# Inverter-demo_1.net
KiCad netlist of a schematic drawn in EAGLE
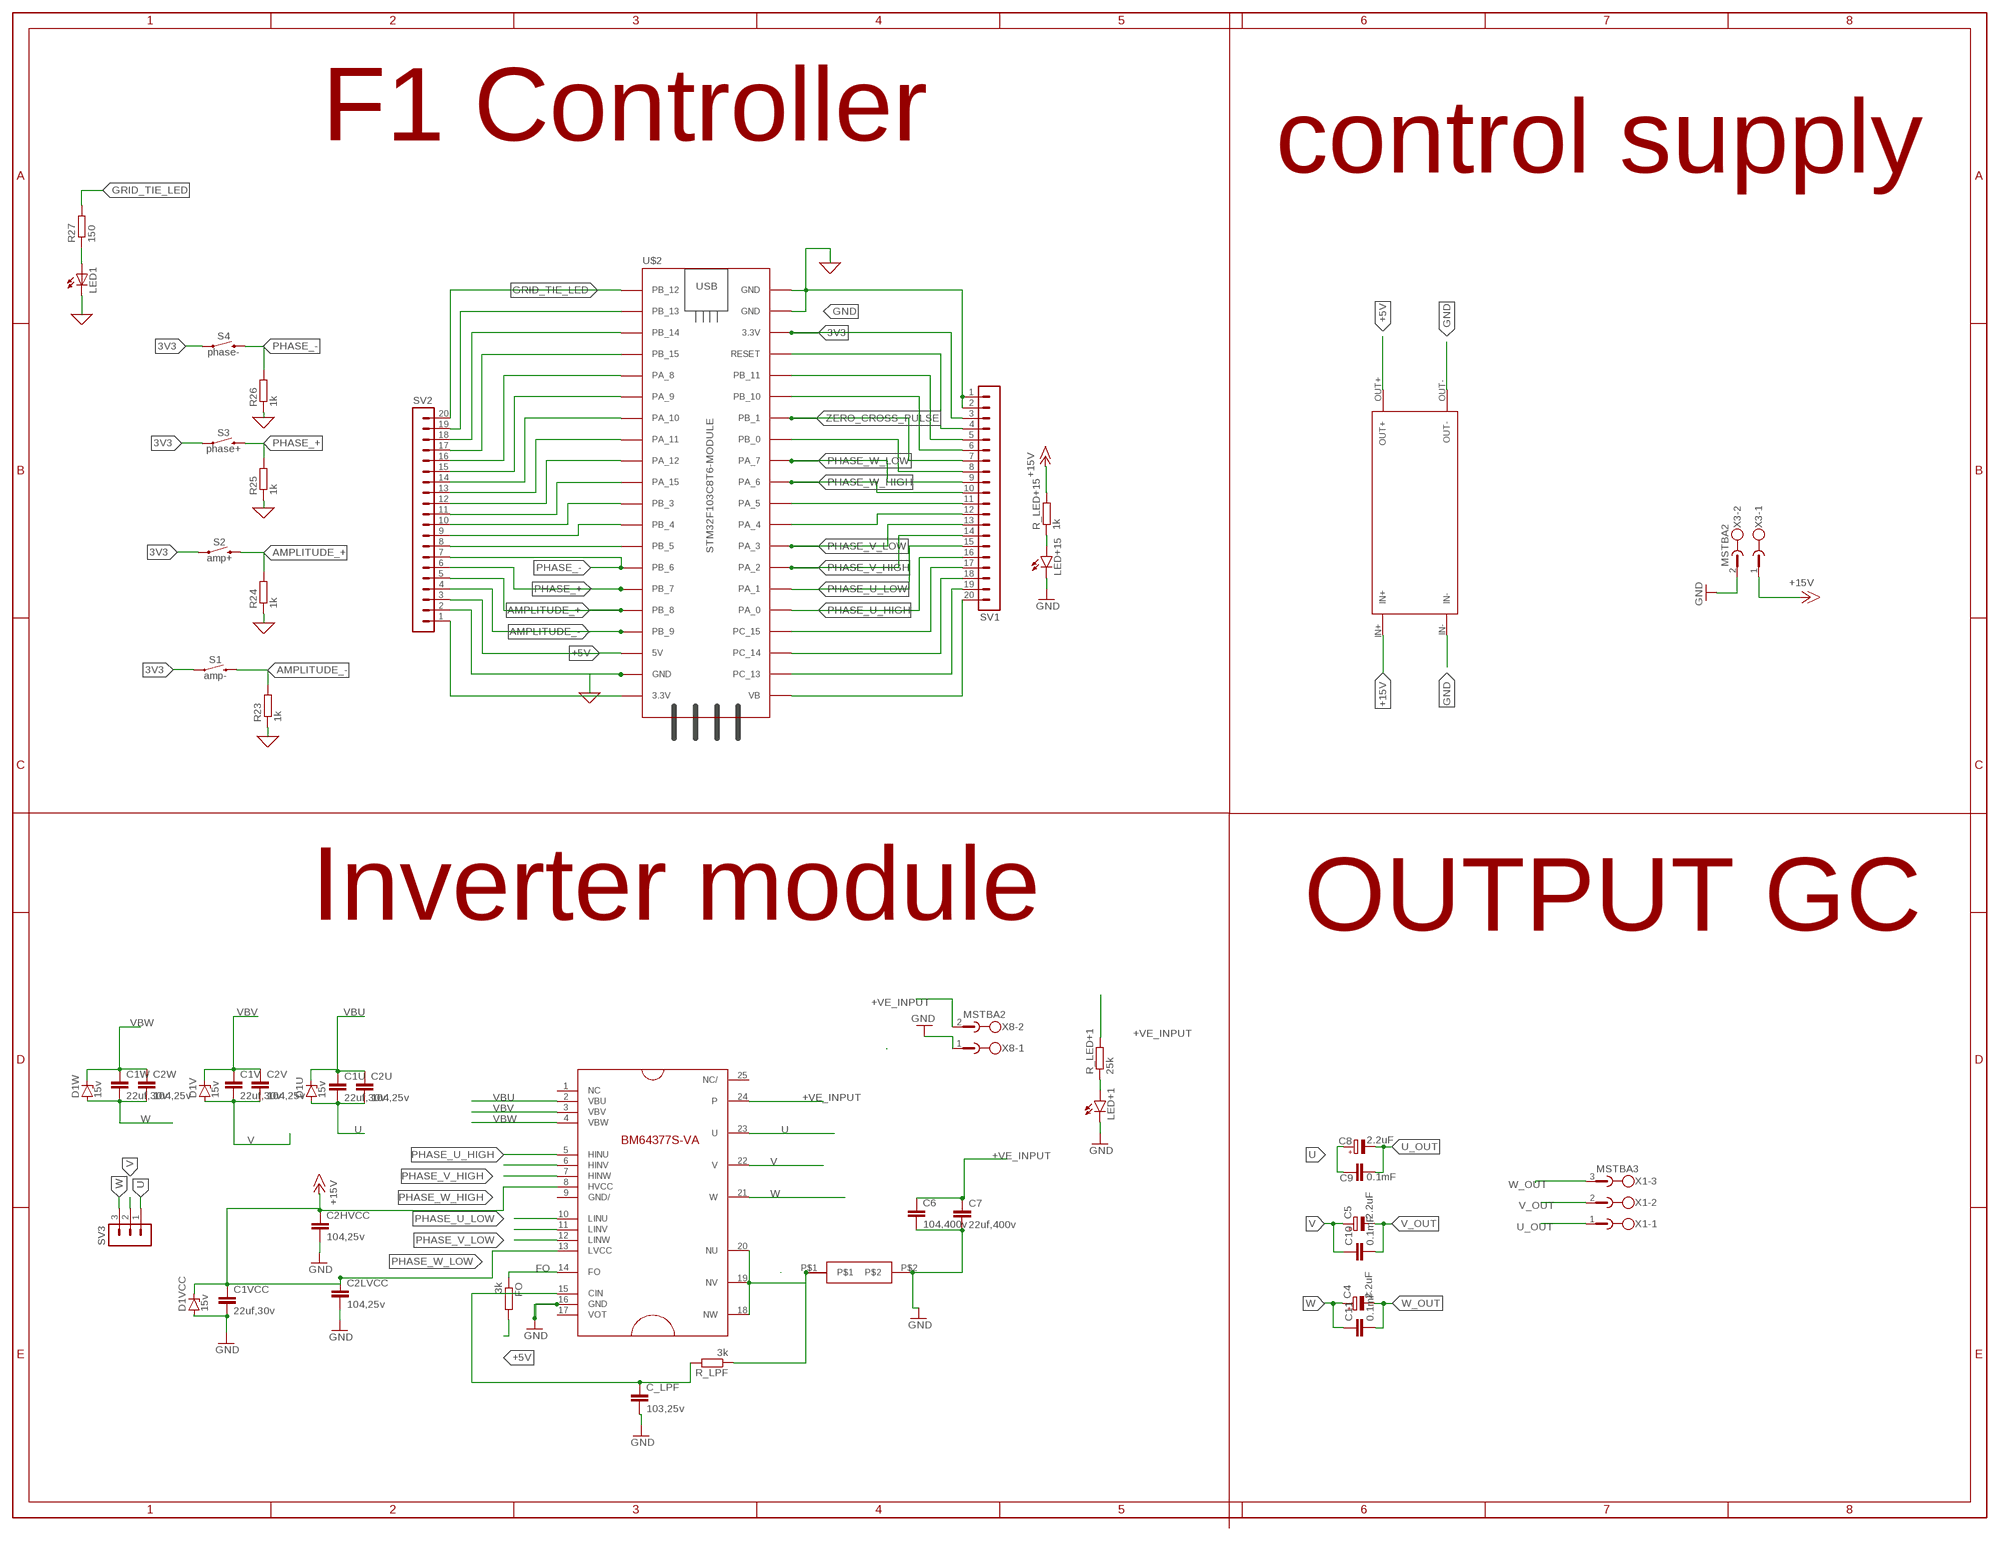
[diagram p0: schematic, sheet 1]

(export (version "E")
  (design (tool "Eeschema 10.0.6"))
  (components
    (comp (ref "C1U")
      (value "22uf,30v")
      (footprint "eagle-import:C050-025X075")
      (libsource (lib "eagle-import") (part "C-EU050-025X075"))
    )
    (comp (ref "C1V")
      (value "22uf,30v")
      (footprint "eagle-import:C050-025X075")
      (libsource (lib "eagle-import") (part "C-EU050-025X075"))
    )
    (comp (ref "C1VCC")
      (value "22uf,30v")
      (footprint "eagle-import:C050-025X075")
      (libsource (lib "eagle-import") (part "C-EU050-025X075"))
    )
    (comp (ref "C1W")
      (value "22uf,30v")
      (footprint "eagle-import:C050-025X075")
      (libsource (lib "eagle-import") (part "C-EU050-025X075"))
    )
    (comp (ref "C2HVCC")
      (value "104,25v")
      (footprint "eagle-import:C050-025X075")
      (libsource (lib "eagle-import") (part "C-EU050-025X075"))
    )
    (comp (ref "C2LVCC")
      (value "104,25v")
      (footprint "eagle-import:C050-025X075")
      (libsource (lib "eagle-import") (part "C-EU050-025X075"))
    )
    (comp (ref "C2U")
      (value "104,25v")
      (footprint "eagle-import:C050-025X075")
      (libsource (lib "eagle-import") (part "C-EU050-025X075"))
    )
    (comp (ref "C2V")
      (value "104,25v")
      (footprint "eagle-import:C050-025X075")
      (libsource (lib "eagle-import") (part "C-EU050-025X075"))
    )
    (comp (ref "C2W")
      (value "104,25v")
      (footprint "eagle-import:C050-025X075")
      (libsource (lib "eagle-import") (part "C-EU050-025X075"))
    )
    (comp (ref "C4")
      (value "2.2uF")
      (footprint "eagle-import:E3,5-8")
      (libsource (lib "eagle-import") (part "CPOL-EUE3.5-8"))
    )
    (comp (ref "C5")
      (value "2.2uF")
      (footprint "eagle-import:E3,5-8")
      (libsource (lib "eagle-import") (part "CPOL-EUE3.5-8"))
    )
    (comp (ref "C6")
      (value "104,400v")
      (footprint "eagle-import:C050-025X075")
      (libsource (lib "eagle-import") (part "C-EU050-025X075"))
    )
    (comp (ref "C7")
      (value "22uf,400v")
      (footprint "eagle-import:C050-025X075")
      (libsource (lib "eagle-import") (part "C-EU050-025X075"))
    )
    (comp (ref "C8")
      (value "2.2uF")
      (footprint "eagle-import:E3,5-8")
      (libsource (lib "eagle-import") (part "CPOL-EUE3.5-8"))
    )
    (comp (ref "C9")
      (value "0.1mF")
      (footprint "eagle-import:C5B5")
      (libsource (lib "eagle-import") (part "C5/5"))
    )
    (comp (ref "C10")
      (value "0.1mF")
      (footprint "eagle-import:C5B5")
      (libsource (lib "eagle-import") (part "C5/5"))
    )
    (comp (ref "C11")
      (value "0.1mF")
      (footprint "eagle-import:C5B5")
      (libsource (lib "eagle-import") (part "C5/5"))
    )
    (comp (ref "C_LPF")
      (value "103,25v")
      (footprint "eagle-import:C050-025X075")
      (libsource (lib "eagle-import") (part "C-EU050-025X075"))
    )
    (comp (ref "D1U")
      (value "15v")
      (footprint "eagle-import:DO34Z7")
      (libsource (lib "eagle-import") (part "ZENER-DIODEDO34-7"))
    )
    (comp (ref "D1V")
      (value "15v")
      (footprint "eagle-import:DO34Z7")
      (libsource (lib "eagle-import") (part "ZENER-DIODEDO34-7"))
    )
    (comp (ref "D1VCC")
      (value "15v")
      (footprint "eagle-import:DO34Z7")
      (libsource (lib "eagle-import") (part "ZENER-DIODEDO34-7"))
    )
    (comp (ref "D1W")
      (value "15v")
      (footprint "eagle-import:DO34Z7")
      (libsource (lib "eagle-import") (part "ZENER-DIODEDO34-7"))
    )
    (comp (ref "FO")
      (value "3k")
      (footprint "eagle-import:0207_10")
      (libsource (lib "eagle-import") (part "R-EU_0207/10"))
    )
    (comp (ref "LED+1")
      (value "LED5MM")
      (footprint "eagle-import:LED5MM")
      (libsource (lib "eagle-import") (part "led_259_LED5MM"))
    )
    (comp (ref "LED+15")
      (value "LED5MM")
      (footprint "eagle-import:LED5MM")
      (libsource (lib "eagle-import") (part "led_259_LED5MM"))
    )
    (comp (ref "LED1")
      (value "LED3MM")
      (footprint "eagle-import:LED3MM")
      (libsource (lib "eagle-import") (part "LED3MM"))
    )
    (comp (ref "R23")
      (value "1k")
      (footprint "eagle-import:0207_10")
      (libsource (lib "eagle-import") (part "R-EU_0207/10"))
    )
    (comp (ref "R24")
      (value "1k")
      (footprint "eagle-import:0207_10")
      (libsource (lib "eagle-import") (part "R-EU_0207/10"))
    )
    (comp (ref "R25")
      (value "1k")
      (footprint "eagle-import:0207_10")
      (libsource (lib "eagle-import") (part "R-EU_0207/10"))
    )
    (comp (ref "R26")
      (value "1k")
      (footprint "eagle-import:0207_10")
      (libsource (lib "eagle-import") (part "R-EU_0207/10"))
    )
    (comp (ref "R27")
      (value "150")
      (footprint "eagle-import:0207_10")
      (libsource (lib "eagle-import") (part "R-EU_0207/10"))
    )
    (comp (ref "R_LED+1")
      (value "25k")
      (footprint "eagle-import:0207_10")
      (libsource (lib "eagle-import") (part "R-EU_0207/10"))
    )
    (comp (ref "R_LED+15")
      (value "1k")
      (footprint "eagle-import:0207_10")
      (libsource (lib "eagle-import") (part "R-EU_0207/10"))
    )
    (comp (ref "R_LPF")
      (value "3k")
      (footprint "eagle-import:0207_10")
      (libsource (lib "eagle-import") (part "R-EU_0207/10"))
    )
    (comp (ref "S1")
      (value "amp-")
      (footprint "eagle-import:TACTILE_SWITCH_PTH_6.0MM")
      (libsource (lib "eagle-import") (part "MOMENTARY-SWITCH-SPST-PTH-6.0MM"))
    )
    (comp (ref "S2")
      (value "amp+")
      (footprint "eagle-import:TACTILE_SWITCH_PTH_6.0MM")
      (libsource (lib "eagle-import") (part "MOMENTARY-SWITCH-SPST-PTH-6.0MM"))
    )
    (comp (ref "S3")
      (value "phase+")
      (footprint "eagle-import:TACTILE_SWITCH_PTH_6.0MM")
      (libsource (lib "eagle-import") (part "MOMENTARY-SWITCH-SPST-PTH-6.0MM"))
    )
    (comp (ref "S4")
      (value "phase-")
      (footprint "eagle-import:TACTILE_SWITCH_PTH_6.0MM")
      (libsource (lib "eagle-import") (part "MOMENTARY-SWITCH-SPST-PTH-6.0MM"))
    )
    (comp (ref "SV1")
      (value "MA20-1")
      (footprint "eagle-import:MA20-1")
      (libsource (lib "eagle-import") (part "MA20-1"))
    )
    (comp (ref "SV2")
      (value "MA20-1")
      (footprint "eagle-import:MA20-1")
      (libsource (lib "eagle-import") (part "MA20-1"))
    )
    (comp (ref "SV3")
      (value "MA03-1")
      (footprint "eagle-import:MA03-1")
      (libsource (lib "eagle-import") (part "MA03-1"))
    )
    (comp (ref "U$1")
      (value "BM64377S-VATHROUGH_HOLE")
      (footprint "eagle-import:IPM-BM64377S-VA")
      (libsource (lib "eagle-import") (part "BM64377S-VATHROUGH_HOLE"))
    )
    (comp (ref "U$2")
      (value "STM32F103C8T6-MODULE")
      (footprint "eagle-import:STM32F103C8T6-MODULE")
      (libsource (lib "eagle-import") (part "STM32F103C8T6-MODULE"))
    )
    (comp (ref "U$3")
      (value "SMALLSHUNT")
      (footprint "eagle-import:SMALLSHUNT")
      (libsource (lib "eagle-import") (part "SMALLSHUNT"))
    )
    (comp (ref "U$4")
      (value "XL4015_DC-DC_CONVERTER")
      (footprint "eagle-import:XL4015_DC-DC_CONVERTER")
      (libsource (lib "eagle-import") (part "XL4015_DC-DC_CONVERTER"))
    )
    (comp (ref "X1")
      (value "MSTBA3")
      (footprint "eagle-import:MSTBA3")
      (fields (field (name "MF") "FARNELL") (field (name "MPN") "1757255"))
      (libsource (lib "eagle-import") (part "MSTBA3"))
    )
    (comp (ref "X3")
      (value "MSTBA2")
      (footprint "eagle-import:MSTBA2")
      (fields (field (name "MF") "FARNELL") (field (name "MPN") "1757242"))
      (libsource (lib "eagle-import") (part "MSTBA2"))
    )
    (comp (ref "X8")
      (value "MSTBA2")
      (footprint "eagle-import:MSTBA2")
      (fields (field (name "MF") "FARNELL") (field (name "MPN") "1757242"))
      (libsource (lib "eagle-import") (part "MSTBA2"))
    )
  )
  (nets
    (net (code "1") (name "+5V") (class "Default")
      (node (ref "FO") (pin "2") (pinfunction "2_2") (pintype "passive"))
      (node (ref "SV2") (pin "3") (pinfunction "3_3") (pintype "passive"))
      (node (ref "U$2") (pin "5V") (pinfunction "5V_5V") (pintype "bidirectional"))
      (node (ref "U$4") (pin "OUT+") (pinfunction "OUT+_OUT+") (pintype "bidirectional"))
    )
    (net (code "2") (name "+15V") (class "Default")
      (node (ref "C1VCC") (pin "1") (pinfunction "1_1") (pintype "passive"))
      (node (ref "C2HVCC") (pin "1") (pinfunction "1_1") (pintype "passive"))
      (node (ref "C2LVCC") (pin "1") (pinfunction "1_1") (pintype "passive"))
      (node (ref "D1VCC") (pin "C") (pinfunction "C_C") (pintype "passive"))
      (node (ref "R_LED+15") (pin "2") (pinfunction "2_2") (pintype "passive"))
      (node (ref "U$1") (pin "13") (pinfunction "LVCC_13") (pintype "bidirectional"))
      (node (ref "U$1") (pin "8") (pinfunction "HVCC_8") (pintype "bidirectional"))
      (node (ref "U$4") (pin "IN+") (pinfunction "IN+_IN+") (pintype "bidirectional"))
      (node (ref "X3") (pin "1") (pinfunction "1_1") (pintype "passive"))
    )
    (net (code "3") (name "/+VE_INPUT") (class "Default")
      (node (ref "C6") (pin "1") (pinfunction "1_1") (pintype "passive"))
      (node (ref "C7") (pin "1") (pinfunction "1_1") (pintype "passive"))
      (node (ref "R_LED+1") (pin "2") (pinfunction "2_2") (pintype "passive"))
      (node (ref "U$1") (pin "24") (pinfunction "P_24") (pintype "bidirectional"))
      (node (ref "X8") (pin "2") (pinfunction "1_2") (pintype "passive"))
    )
    (net (code "4") (name "/FO") (class "Default")
      (node (ref "FO") (pin "1") (pinfunction "1_1") (pintype "passive"))
      (node (ref "U$1") (pin "14") (pinfunction "FO_14") (pintype "bidirectional"))
    )
    (net (code "5") (name "/VBU") (class "Default")
      (node (ref "C1U") (pin "1") (pinfunction "1_1") (pintype "passive"))
      (node (ref "C2U") (pin "1") (pinfunction "1_1") (pintype "passive"))
      (node (ref "D1U") (pin "C") (pinfunction "C_C") (pintype "passive"))
      (node (ref "U$1") (pin "2") (pinfunction "VBU_2") (pintype "bidirectional"))
    )
    (net (code "6") (name "/VBV") (class "Default")
      (node (ref "C1V") (pin "1") (pinfunction "1_1") (pintype "passive"))
      (node (ref "C2V") (pin "1") (pinfunction "1_1") (pintype "passive"))
      (node (ref "D1V") (pin "C") (pinfunction "C_C") (pintype "passive"))
      (node (ref "U$1") (pin "3") (pinfunction "VBV_3") (pintype "bidirectional"))
    )
    (net (code "7") (name "/VBW") (class "Default")
      (node (ref "C1W") (pin "1") (pinfunction "1_1") (pintype "passive"))
      (node (ref "C2W") (pin "1") (pinfunction "1_1") (pintype "passive"))
      (node (ref "D1W") (pin "C") (pinfunction "C_C") (pintype "passive"))
      (node (ref "U$1") (pin "4") (pinfunction "VBW_4") (pintype "bidirectional"))
    )
    (net (code "8") (name "3V3") (class "Default")
      (node (ref "S1") (pin "1") (pinfunction "1_1") (pintype "passive"))
      (node (ref "S2") (pin "1") (pinfunction "1_1") (pintype "passive"))
      (node (ref "S3") (pin "1") (pinfunction "1_1") (pintype "passive"))
      (node (ref "S4") (pin "1") (pinfunction "1_1") (pintype "passive"))
      (node (ref "SV1") (pin "3") (pinfunction "3_3") (pintype "passive"))
      (node (ref "U$2") (pin "3.3V_2") (pinfunction "3.3V_3.3V_2") (pintype "bidirectional"))
    )
    (net (code "9") (name "AMPLITUDE_+") (class "Default")
      (node (ref "R24") (pin "2") (pinfunction "2_2") (pintype "passive"))
      (node (ref "S2") (pin "3") (pinfunction "2_3") (pintype "passive"))
      (node (ref "SV2") (pin "5") (pinfunction "5_5") (pintype "passive"))
      (node (ref "U$2") (pin "PB_8") (pinfunction "PB_8_PB_8") (pintype "bidirectional"))
    )
    (net (code "10") (name "AMPLITUDE_-") (class "Default")
      (node (ref "R23") (pin "2") (pinfunction "2_2") (pintype "passive"))
      (node (ref "S1") (pin "3") (pinfunction "2_3") (pintype "passive"))
      (node (ref "SV2") (pin "4") (pinfunction "4_4") (pintype "passive"))
      (node (ref "U$2") (pin "PB_9") (pinfunction "PB_9_PB_9") (pintype "bidirectional"))
    )
    (net (code "11") (name "GND") (class "Default")
      (node (ref "C1VCC") (pin "2") (pinfunction "2_2") (pintype "passive"))
      (node (ref "C2HVCC") (pin "2") (pinfunction "2_2") (pintype "passive"))
      (node (ref "C2LVCC") (pin "2") (pinfunction "2_2") (pintype "passive"))
      (node (ref "C6") (pin "2") (pinfunction "2_2") (pintype "passive"))
      (node (ref "C7") (pin "2") (pinfunction "2_2") (pintype "passive"))
      (node (ref "C_LPF") (pin "2") (pinfunction "2_2") (pintype "passive"))
      (node (ref "D1VCC") (pin "A") (pinfunction "A_A") (pintype "passive"))
      (node (ref "LED+1") (pin "K") (pinfunction "C_K") (pintype "passive"))
      (node (ref "LED+15") (pin "K") (pinfunction "C_K") (pintype "passive"))
      (node (ref "LED1") (pin "K") (pinfunction "C_K") (pintype "passive"))
      (node (ref "R23") (pin "1") (pinfunction "1_1") (pintype "passive"))
      (node (ref "R24") (pin "1") (pinfunction "1_1") (pintype "passive"))
      (node (ref "R25") (pin "1") (pinfunction "1_1") (pintype "passive"))
      (node (ref "R26") (pin "1") (pinfunction "1_1") (pintype "passive"))
      (node (ref "SV1") (pin "1") (pinfunction "1_1") (pintype "passive"))
      (node (ref "SV1") (pin "2") (pinfunction "2_2") (pintype "passive"))
      (node (ref "SV2") (pin "2") (pinfunction "2_2") (pintype "passive"))
      (node (ref "U$1") (pin "16") (pinfunction "GND_16") (pintype "bidirectional"))
      (node (ref "U$2") (pin "GND_1") (pinfunction "GND_GND_1") (pintype "bidirectional"))
      (node (ref "U$2") (pin "GND_2") (pinfunction "GND_GND_2") (pintype "bidirectional"))
      (node (ref "U$2") (pin "GND_3") (pinfunction "GND_GND_3") (pintype "power_in"))
      (node (ref "U$3") (pin "P$2") (pinfunction "P$2_P$2") (pintype "bidirectional"))
      (node (ref "U$4") (pin "IN-") (pinfunction "IN-_IN-") (pintype "bidirectional"))
      (node (ref "U$4") (pin "OUT-") (pinfunction "OUT-_OUT-") (pintype "bidirectional"))
      (node (ref "X3") (pin "2") (pinfunction "1_2") (pintype "passive"))
      (node (ref "X8") (pin "1") (pinfunction "1_1") (pintype "passive"))
    )
    (net (code "12") (name "GRID_TIE_LED") (class "Default")
      (node (ref "R27") (pin "2") (pinfunction "2_2") (pintype "passive"))
      (node (ref "SV2") (pin "20") (pinfunction "20_20") (pintype "passive"))
      (node (ref "U$2") (pin "PB_12") (pinfunction "PB_12_PB_12") (pintype "bidirectional"))
    )
    (net (code "13") (name "Net-(LED+1-PadA)") (class "Default")
      (node (ref "LED+1") (pin "A") (pinfunction "A_A") (pintype "passive"))
      (node (ref "R_LED+1") (pin "1") (pinfunction "1_1") (pintype "passive"))
    )
    (net (code "14") (name "Net-(LED+15-PadA)") (class "Default")
      (node (ref "LED+15") (pin "A") (pinfunction "A_A") (pintype "passive"))
      (node (ref "R_LED+15") (pin "1") (pinfunction "1_1") (pintype "passive"))
    )
    (net (code "15") (name "Net-(LED1-PadA)") (class "Default")
      (node (ref "LED1") (pin "A") (pinfunction "A_A") (pintype "passive"))
      (node (ref "R27") (pin "1") (pinfunction "1_1") (pintype "passive"))
    )
    (net (code "16") (name "Net-(SV1-Pad4)") (class "Default")
      (node (ref "SV1") (pin "4") (pinfunction "4_4") (pintype "passive"))
      (node (ref "U$2") (pin "RESET") (pinfunction "RESET_RESET") (pintype "bidirectional"))
    )
    (net (code "17") (name "Net-(SV1-Pad5)") (class "Default")
      (node (ref "SV1") (pin "5") (pinfunction "5_5") (pintype "passive"))
      (node (ref "U$2") (pin "PB_11") (pinfunction "PB_11_PB_11") (pintype "bidirectional"))
    )
    (net (code "18") (name "Net-(SV1-Pad6)") (class "Default")
      (node (ref "SV1") (pin "6") (pinfunction "6_6") (pintype "passive"))
      (node (ref "U$2") (pin "PB_10") (pinfunction "PB_10_PB_10") (pintype "bidirectional"))
    )
    (net (code "19") (name "Net-(SV1-Pad8)") (class "Default")
      (node (ref "SV1") (pin "8") (pinfunction "8_8") (pintype "passive"))
      (node (ref "U$2") (pin "PB_0") (pinfunction "PB_0_PB_0") (pintype "bidirectional"))
    )
    (net (code "20") (name "Net-(SV1-Pad11)") (class "Default")
      (node (ref "SV1") (pin "11") (pinfunction "11_11") (pintype "passive"))
      (node (ref "U$2") (pin "PA_5") (pinfunction "PA_5_PA_5") (pintype "bidirectional"))
    )
    (net (code "21") (name "Net-(SV1-Pad12)") (class "Default")
      (node (ref "SV1") (pin "12") (pinfunction "12_12") (pintype "passive"))
      (node (ref "U$2") (pin "PA_4") (pinfunction "PA_4_PA_4") (pintype "bidirectional"))
    )
    (net (code "22") (name "Net-(SV1-Pad17)") (class "Default")
      (node (ref "SV1") (pin "17") (pinfunction "17_17") (pintype "passive"))
      (node (ref "U$2") (pin "PC_15") (pinfunction "PC_15_PC_15") (pintype "bidirectional"))
    )
    (net (code "23") (name "Net-(SV1-Pad18)") (class "Default")
      (node (ref "SV1") (pin "18") (pinfunction "18_18") (pintype "passive"))
      (node (ref "U$2") (pin "PC_14") (pinfunction "PC_14_PC_14") (pintype "bidirectional"))
    )
    (net (code "24") (name "Net-(SV1-Pad19)") (class "Default")
      (node (ref "SV1") (pin "19") (pinfunction "19_19") (pintype "passive"))
      (node (ref "U$2") (pin "PC_13") (pinfunction "PC_13_PC_13") (pintype "bidirectional"))
    )
    (net (code "25") (name "Net-(SV1-Pad20)") (class "Default")
      (node (ref "SV1") (pin "20") (pinfunction "20_20") (pintype "passive"))
      (node (ref "U$2") (pin "VB") (pinfunction "VB_VB") (pintype "bidirectional"))
    )
    (net (code "26") (name "Net-(SV2-Pad1)") (class "Default")
      (node (ref "SV2") (pin "1") (pinfunction "1_1") (pintype "passive"))
      (node (ref "U$2") (pin "3.3V_1") (pinfunction "3.3V_3.3V_1") (pintype "bidirectional"))
    )
    (net (code "27") (name "Net-(SV2-Pad8)") (class "Default")
      (node (ref "SV2") (pin "8") (pinfunction "8_8") (pintype "passive"))
      (node (ref "U$2") (pin "PB_5") (pinfunction "PB_5_PB_5") (pintype "bidirectional"))
    )
    (net (code "28") (name "Net-(SV2-Pad9)") (class "Default")
      (node (ref "SV2") (pin "9") (pinfunction "9_9") (pintype "passive"))
      (node (ref "U$2") (pin "PB_4") (pinfunction "PB_4_PB_4") (pintype "bidirectional"))
    )
    (net (code "29") (name "Net-(SV2-Pad10)") (class "Default")
      (node (ref "SV2") (pin "10") (pinfunction "10_10") (pintype "passive"))
      (node (ref "U$2") (pin "PB_3") (pinfunction "PB_3_PB_3") (pintype "bidirectional"))
    )
    (net (code "30") (name "Net-(SV2-Pad11)") (class "Default")
      (node (ref "SV2") (pin "11") (pinfunction "11_11") (pintype "passive"))
      (node (ref "U$2") (pin "PA_15") (pinfunction "PA_15_PA_15") (pintype "bidirectional"))
    )
    (net (code "31") (name "Net-(SV2-Pad12)") (class "Default")
      (node (ref "SV2") (pin "12") (pinfunction "12_12") (pintype "passive"))
      (node (ref "U$2") (pin "PA_12") (pinfunction "PA_12_PA_12") (pintype "bidirectional"))
    )
    (net (code "32") (name "Net-(SV2-Pad13)") (class "Default")
      (node (ref "SV2") (pin "13") (pinfunction "13_13") (pintype "passive"))
      (node (ref "U$2") (pin "PA_11") (pinfunction "PA_11_PA_11") (pintype "bidirectional"))
    )
    (net (code "33") (name "Net-(SV2-Pad14)") (class "Default")
      (node (ref "SV2") (pin "14") (pinfunction "14_14") (pintype "passive"))
      (node (ref "U$2") (pin "PA_10") (pinfunction "PA_10_PA_10") (pintype "bidirectional"))
    )
    (net (code "34") (name "Net-(SV2-Pad15)") (class "Default")
      (node (ref "SV2") (pin "15") (pinfunction "15_15") (pintype "passive"))
      (node (ref "U$2") (pin "PA_9") (pinfunction "PA_9_PA_9") (pintype "bidirectional"))
    )
    (net (code "35") (name "Net-(SV2-Pad16)") (class "Default")
      (node (ref "SV2") (pin "16") (pinfunction "16_16") (pintype "passive"))
      (node (ref "U$2") (pin "PA_8") (pinfunction "PA_8_PA_8") (pintype "bidirectional"))
    )
    (net (code "36") (name "Net-(SV2-Pad17)") (class "Default")
      (node (ref "SV2") (pin "17") (pinfunction "17_17") (pintype "passive"))
      (node (ref "U$2") (pin "PB_15") (pinfunction "PB_15_PB_15") (pintype "bidirectional"))
    )
    (net (code "37") (name "Net-(SV2-Pad18)") (class "Default")
      (node (ref "SV2") (pin "18") (pinfunction "18_18") (pintype "passive"))
      (node (ref "U$2") (pin "PB_14") (pinfunction "PB_14_PB_14") (pintype "bidirectional"))
    )
    (net (code "38") (name "Net-(SV2-Pad19)") (class "Default")
      (node (ref "SV2") (pin "19") (pinfunction "19_19") (pintype "passive"))
      (node (ref "U$2") (pin "PB_13") (pinfunction "PB_13_PB_13") (pintype "bidirectional"))
    )
    (net (code "39") (name "Net-(U$1-CIN)") (class "Default")
      (node (ref "C_LPF") (pin "1") (pinfunction "1_1") (pintype "passive"))
      (node (ref "R_LPF") (pin "2") (pinfunction "2_2") (pintype "passive"))
      (node (ref "U$1") (pin "15") (pinfunction "CIN_15") (pintype "bidirectional"))
    )
    (net (code "40") (name "Net-(U$1-NU)") (class "Default")
      (node (ref "R_LPF") (pin "1") (pinfunction "1_1") (pintype "passive"))
      (node (ref "U$1") (pin "18") (pinfunction "NW_18") (pintype "bidirectional"))
      (node (ref "U$1") (pin "19") (pinfunction "NV_19") (pintype "bidirectional"))
      (node (ref "U$1") (pin "20") (pinfunction "NU_20") (pintype "bidirectional"))
      (node (ref "U$3") (pin "P$1") (pinfunction "P$1_P$1") (pintype "bidirectional"))
    )
    (net (code "41") (name "PHASE_+") (class "Default")
      (node (ref "R25") (pin "2") (pinfunction "2_2") (pintype "passive"))
      (node (ref "S3") (pin "3") (pinfunction "2_3") (pintype "passive"))
      (node (ref "SV2") (pin "6") (pinfunction "6_6") (pintype "passive"))
      (node (ref "U$2") (pin "PB_7") (pinfunction "PB_7_PB_7") (pintype "bidirectional"))
    )
    (net (code "42") (name "PHASE_-") (class "Default")
      (node (ref "R26") (pin "2") (pinfunction "2_2") (pintype "passive"))
      (node (ref "S4") (pin "3") (pinfunction "2_3") (pintype "passive"))
      (node (ref "SV2") (pin "7") (pinfunction "7_7") (pintype "passive"))
      (node (ref "U$2") (pin "PB_6") (pinfunction "PB_6_PB_6") (pintype "bidirectional"))
    )
    (net (code "43") (name "PHASE_U_HIGH") (class "Default")
      (node (ref "SV1") (pin "16") (pinfunction "16_16") (pintype "passive"))
      (node (ref "U$1") (pin "5") (pinfunction "HINU_5") (pintype "bidirectional"))
      (node (ref "U$2") (pin "PA_0") (pinfunction "PA_0_PA_0") (pintype "bidirectional"))
    )
    (net (code "44") (name "PHASE_U_LOW") (class "Default")
      (node (ref "SV1") (pin "15") (pinfunction "15_15") (pintype "passive"))
      (node (ref "U$1") (pin "10") (pinfunction "LINU_10") (pintype "bidirectional"))
      (node (ref "U$2") (pin "PA_1") (pinfunction "PA_1_PA_1") (pintype "bidirectional"))
    )
    (net (code "45") (name "PHASE_V_HIGH") (class "Default")
      (node (ref "SV1") (pin "14") (pinfunction "14_14") (pintype "passive"))
      (node (ref "U$1") (pin "6") (pinfunction "HINV_6") (pintype "bidirectional"))
      (node (ref "U$2") (pin "PA_2") (pinfunction "PA_2_PA_2") (pintype "bidirectional"))
    )
    (net (code "46") (name "PHASE_V_LOW") (class "Default")
      (node (ref "SV1") (pin "13") (pinfunction "13_13") (pintype "passive"))
      (node (ref "U$1") (pin "11") (pinfunction "LINV_11") (pintype "bidirectional"))
      (node (ref "U$2") (pin "PA_3") (pinfunction "PA_3_PA_3") (pintype "bidirectional"))
    )
    (net (code "47") (name "PHASE_W_HIGH") (class "Default")
      (node (ref "SV1") (pin "10") (pinfunction "10_10") (pintype "passive"))
      (node (ref "U$1") (pin "7") (pinfunction "HINW_7") (pintype "bidirectional"))
      (node (ref "U$2") (pin "PA_6") (pinfunction "PA_6_PA_6") (pintype "bidirectional"))
    )
    (net (code "48") (name "PHASE_W_LOW") (class "Default")
      (node (ref "SV1") (pin "9") (pinfunction "9_9") (pintype "passive"))
      (node (ref "U$1") (pin "12") (pinfunction "LINW_12") (pintype "bidirectional"))
      (node (ref "U$2") (pin "PA_7") (pinfunction "PA_7_PA_7") (pintype "bidirectional"))
    )
    (net (code "49") (name "U") (class "Default")
      (node (ref "C1U") (pin "2") (pinfunction "2_2") (pintype "passive"))
      (node (ref "C2U") (pin "2") (pinfunction "2_2") (pintype "passive"))
      (node (ref "C8") (pin "+") (pinfunction "+_+") (pintype "passive"))
      (node (ref "C9") (pin "1") (pinfunction "1_1") (pintype "passive"))
      (node (ref "D1U") (pin "A") (pinfunction "A_A") (pintype "passive"))
      (node (ref "SV3") (pin "1") (pinfunction "1_1") (pintype "passive"))
      (node (ref "U$1") (pin "23") (pinfunction "U_23") (pintype "bidirectional"))
    )
    (net (code "50") (name "U_OUT") (class "Default")
      (node (ref "C8") (pin "-") (pinfunction "-_-") (pintype "passive"))
      (node (ref "C9") (pin "2") (pinfunction "2_2") (pintype "passive"))
      (node (ref "X1") (pin "1") (pinfunction "1_1") (pintype "passive"))
    )
    (net (code "51") (name "V") (class "Default")
      (node (ref "C10") (pin "1") (pinfunction "1_1") (pintype "passive"))
      (node (ref "C1V") (pin "2") (pinfunction "2_2") (pintype "passive"))
      (node (ref "C2V") (pin "2") (pinfunction "2_2") (pintype "passive"))
      (node (ref "C5") (pin "+") (pinfunction "+_+") (pintype "passive"))
      (node (ref "D1V") (pin "A") (pinfunction "A_A") (pintype "passive"))
      (node (ref "SV3") (pin "2") (pinfunction "2_2") (pintype "passive"))
      (node (ref "U$1") (pin "22") (pinfunction "V_22") (pintype "bidirectional"))
    )
    (net (code "52") (name "V_OUT") (class "Default")
      (node (ref "C10") (pin "2") (pinfunction "2_2") (pintype "passive"))
      (node (ref "C5") (pin "-") (pinfunction "-_-") (pintype "passive"))
      (node (ref "X1") (pin "2") (pinfunction "1_2") (pintype "passive"))
    )
    (net (code "53") (name "W") (class "Default")
      (node (ref "C11") (pin "1") (pinfunction "1_1") (pintype "passive"))
      (node (ref "C1W") (pin "2") (pinfunction "2_2") (pintype "passive"))
      (node (ref "C2W") (pin "2") (pinfunction "2_2") (pintype "passive"))
      (node (ref "C4") (pin "+") (pinfunction "+_+") (pintype "passive"))
      (node (ref "D1W") (pin "A") (pinfunction "A_A") (pintype "passive"))
      (node (ref "SV3") (pin "3") (pinfunction "3_3") (pintype "passive"))
      (node (ref "U$1") (pin "21") (pinfunction "W_21") (pintype "bidirectional"))
    )
    (net (code "54") (name "W_OUT") (class "Default")
      (node (ref "C11") (pin "2") (pinfunction "2_2") (pintype "passive"))
      (node (ref "C4") (pin "-") (pinfunction "-_-") (pintype "passive"))
      (node (ref "X1") (pin "3") (pinfunction "1_3") (pintype "passive"))
    )
    (net (code "55") (name "ZERO_CROSS_PULSE") (class "Default")
      (node (ref "SV1") (pin "7") (pinfunction "7_7") (pintype "passive"))
      (node (ref "U$2") (pin "PB_1") (pinfunction "PB_1_PB_1") (pintype "bidirectional"))
    )
    (net (code "56") (name "unconnected-(U$1-GND{slash}-Pad9)") (class "Default")
      (node (ref "U$1") (pin "9") (pinfunction "GND/_9") (pintype "bidirectional"))
    )
    (net (code "57") (name "unconnected-(U$1-NC-Pad1)") (class "Default")
      (node (ref "U$1") (pin "1") (pinfunction "NC_1") (pintype "bidirectional"))
    )
    (net (code "58") (name "unconnected-(U$1-NC{slash}-Pad25)") (class "Default")
      (node (ref "U$1") (pin "25") (pinfunction "NC/_25") (pintype "bidirectional"))
    )
    (net (code "59") (name "unconnected-(U$1-VOT-Pad17)") (class "Default")
      (node (ref "U$1") (pin "17") (pinfunction "VOT_17") (pintype "bidirectional"))
    )
  )
)
